# IO_FMU_REV_1B.net
KiCad netlist of a schematic drawn in Altium Designer
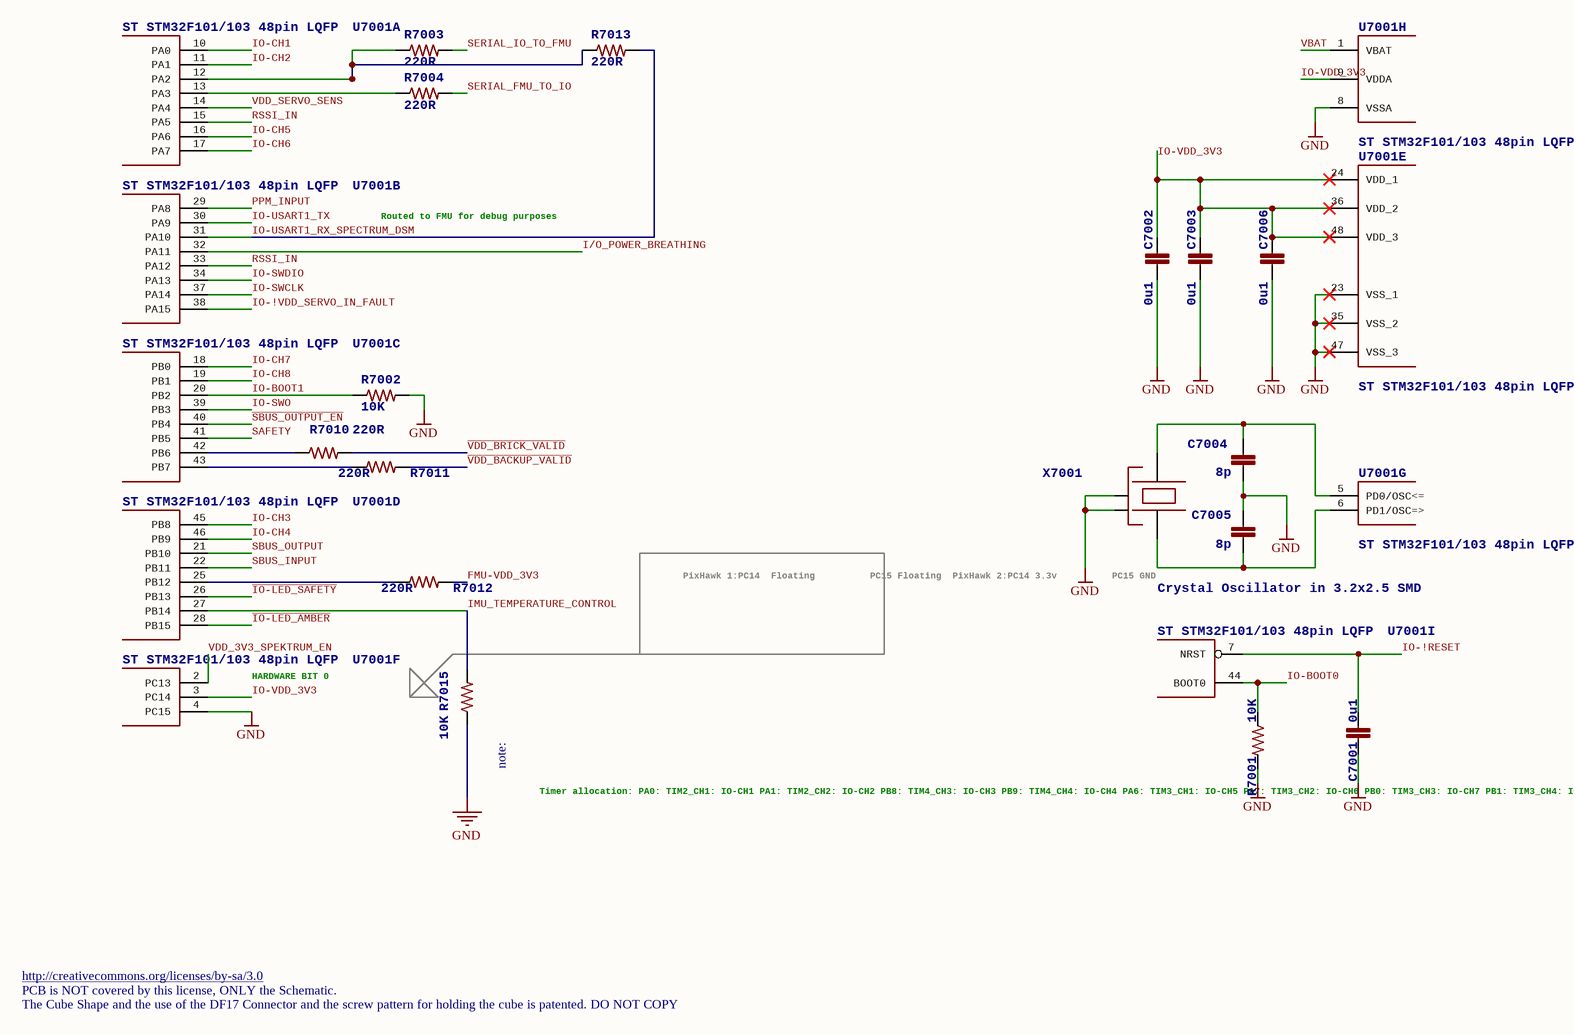
[diagram p0: IO_FMU_REV_1B.SchDoc]

(export (version "E")
  (design (tool "Eeschema 10.0.6"))
  (components
    (comp (ref "C7001")
      (value "0u1")
      (footprint "0402-CAP")
      (description "CAP CER 0.1UF 16V Y5V 0402")
      (libsource (lib "") (part "CAP0402_1"))
    )
    (comp (ref "C7002")
      (value "0u1")
      (footprint "0402-CAP")
      (description "CAP CER 0.1UF 16V Y5V 0402")
      (libsource (lib "pixhawk2") (part "CAP0402"))
    )
    (comp (ref "C7003")
      (value "0u1")
      (footprint "0402-CAP")
      (description "CAP CER 0.1UF 16V Y5V 0402")
      (libsource (lib "pixhawk2") (part "CAP0402"))
    )
    (comp (ref "C7004")
      (value "8p")
      (footprint "0402-CAP")
      (description "CAP CER 8PF 50V C0G 0402")
      (libsource (lib "pixhawk2") (part "CAP0402"))
    )
    (comp (ref "C7005")
      (value "8p")
      (footprint "0402-CAP")
      (description "CAP CER 8PF 50V C0G 0402")
      (libsource (lib "pixhawk2") (part "CAP0402"))
    )
    (comp (ref "C7006")
      (value "0u1")
      (footprint "0402-CAP")
      (description "CAP CER 0.1UF 16V Y5V 0402")
      (libsource (lib "pixhawk2") (part "CAP0402"))
    )
    (comp (ref "R7001")
      (value "10K")
      (footprint "0402-RES")
      (description "RES 10K OHM 1/16W 1% 0402 SMD")
      (libsource (lib "pixhawk2") (part "RESISTOR0402-RES"))
    )
    (comp (ref "R7002")
      (value "10K")
      (footprint "0402-RES")
      (description "RES 10K OHM 1/16W 1% 0402 SMD")
      (libsource (lib "pixhawk2") (part "RESISTOR0402-RES"))
    )
    (comp (ref "R7003")
      (value "220R")
      (footprint "0402-RES")
      (description "RES 220 OHM 1/16W 1% 0402 SMD")
      (libsource (lib "pixhawk2") (part "RESISTOR0402-RES"))
    )
    (comp (ref "R7004")
      (value "220R")
      (footprint "0402-RES")
      (description "RES 220 OHM 1/16W 1% 0402 SMD")
      (libsource (lib "pixhawk2") (part "RESISTOR0402-RES"))
    )
    (comp (ref "R7010")
      (value "220R")
      (footprint "0402-RES")
      (description "RES 220 OHM 1/16W 1% 0402 SMD")
      (libsource (lib "pixhawk2") (part "RESISTOR0402-RES"))
    )
    (comp (ref "R7011")
      (value "220R")
      (footprint "0402-RES")
      (description "RES 220 OHM 1/16W 1% 0402 SMD")
      (libsource (lib "pixhawk2") (part "RESISTOR0402-RES"))
    )
    (comp (ref "R7012")
      (value "220R")
      (footprint "0402-RES")
      (description "RES 220 OHM 1/16W 1% 0402 SMD")
      (libsource (lib "pixhawk2") (part "RESISTOR0402-RES"))
    )
    (comp (ref "R7013")
      (value "220R")
      (footprint "0402-RES")
      (description "RES 220 OHM 1/16W 1% 0402 SMD")
      (libsource (lib "pixhawk2") (part "RESISTOR0402-RES"))
    )
    (comp (ref "R7015")
      (value "10K")
      (footprint "0402-RES")
      (description "RES 10K OHM 1/16W 1% 0402 SMD")
      (libsource (lib "pixhawk2") (part "RESISTOR0402-RES"))
    )
    (comp (ref "U7001")
      (value "ST STM32F101/103 48pin LQFP")
      (footprint "TQFP48")
      (description "MCU 32BIT ARM 64K FLASH 48LQFP")
      (libsource (lib "pixhawk2") (part "STM32F10XCXT6"))
    )
    (comp (ref "X7001")
      (value "Crystal Oscillator in 3.2x2.5 SMD")
      (footprint "OSCILLATOR-3.2X2.5")
      (description "CRYSTAL 24MHZ 8PF SMD")
      (libsource (lib "pixhawk2") (part "OSCILLATOR-3.2X2.5"))
    )
  )
  (nets
    (net (code "1") (name "/FMU-VDD_3V3") (class "Default")
      (node (ref "R7012") (pin "P$2") (pinfunction "2_P$2") (pintype "passive"))
    )
    (net (code "2") (name "/IMU_TEMPERATURE_CONTROL") (class "Default")
      (node (ref "R7015") (pin "P$2") (pinfunction "2_P$2") (pintype "passive"))
      (node (ref "U7001") (pin "27") (pinfunction "PB14_27") (pintype "passive"))
    )
    (net (code "3") (name "/IO-!RESET") (class "Default")
      (node (ref "C7001") (pin "P$2") (pinfunction "2_P$2") (pintype "passive"))
      (node (ref "U7001") (pin "7") (pinfunction "NRST_7") (pintype "passive"))
    )
    (net (code "4") (name "/IO-!VDD_SERVO_IN_FAULT") (class "Default")
      (node (ref "U7001") (pin "38") (pinfunction "PA15_38") (pintype "passive"))
    )
    (net (code "5") (name "/IO-BOOT0") (class "Default")
      (node (ref "R7001") (pin "P$1") (pinfunction "1_P$1") (pintype "passive"))
      (node (ref "U7001") (pin "44") (pinfunction "BOOT0_44") (pintype "passive"))
    )
    (net (code "6") (name "/IO-BOOT1") (class "Default")
      (node (ref "R7002") (pin "P$1") (pinfunction "1_P$1") (pintype "passive"))
      (node (ref "U7001") (pin "20") (pinfunction "PB2_20") (pintype "passive"))
    )
    (net (code "7") (name "/IO-CH1") (class "Default")
      (node (ref "U7001") (pin "10") (pinfunction "PA0_10") (pintype "passive"))
    )
    (net (code "8") (name "/IO-CH2") (class "Default")
      (node (ref "U7001") (pin "11") (pinfunction "PA1_11") (pintype "passive"))
    )
    (net (code "9") (name "/IO-CH3") (class "Default")
      (node (ref "U7001") (pin "45") (pinfunction "PB8_45") (pintype "passive"))
    )
    (net (code "10") (name "/IO-CH4") (class "Default")
      (node (ref "U7001") (pin "46") (pinfunction "PB9_46") (pintype "passive"))
    )
    (net (code "11") (name "/IO-CH5") (class "Default")
      (node (ref "U7001") (pin "16") (pinfunction "PA6_16") (pintype "passive"))
    )
    (net (code "12") (name "/IO-CH6") (class "Default")
      (node (ref "U7001") (pin "17") (pinfunction "PA7_17") (pintype "passive"))
    )
    (net (code "13") (name "/IO-CH7") (class "Default")
      (node (ref "U7001") (pin "18") (pinfunction "PB0_18") (pintype "passive"))
    )
    (net (code "14") (name "/IO-CH8") (class "Default")
      (node (ref "U7001") (pin "19") (pinfunction "PB1_19") (pintype "passive"))
    )
    (net (code "15") (name "/IO-SWCLK") (class "Default")
      (node (ref "U7001") (pin "37") (pinfunction "PA14_37") (pintype "passive"))
    )
    (net (code "16") (name "/IO-SWDIO") (class "Default")
      (node (ref "U7001") (pin "34") (pinfunction "PA13_34") (pintype "passive"))
    )
    (net (code "17") (name "/IO-SWO") (class "Default")
      (node (ref "U7001") (pin "39") (pinfunction "PB3_39") (pintype "passive"))
    )
    (net (code "18") (name "/IO-USART1_RX_SPECTRUM_DSM") (class "Default")
      (node (ref "R7013") (pin "P$2") (pinfunction "2_P$2") (pintype "passive"))
      (node (ref "U7001") (pin "31") (pinfunction "PA10_31") (pintype "passive"))
    )
    (net (code "19") (name "/IO-USART1_TX") (class "Default")
      (node (ref "U7001") (pin "30") (pinfunction "PA9_30") (pintype "passive"))
    )
    (net (code "20") (name "/IO-VDD_3V3") (class "Default")
      (node (ref "C7002") (pin "P$1") (pinfunction "1_P$1") (pintype "passive"))
      (node (ref "C7003") (pin "P$1") (pinfunction "1_P$1") (pintype "passive"))
      (node (ref "C7006") (pin "P$1") (pinfunction "1_P$1") (pintype "passive"))
      (node (ref "U7001") (pin "24") (pinfunction "VDD_1_24") (pintype "power_in"))
      (node (ref "U7001") (pin "3") (pinfunction "PC14_3") (pintype "passive"))
      (node (ref "U7001") (pin "36") (pinfunction "VDD_2_36") (pintype "power_in"))
      (node (ref "U7001") (pin "48") (pinfunction "VDD_3_48") (pintype "power_in"))
      (node (ref "U7001") (pin "9") (pinfunction "VDDA_9") (pintype "power_in"))
    )
    (net (code "21") (name "/I{slash}O_POWER_BREATHING") (class "Default")
      (node (ref "U7001") (pin "32") (pinfunction "PA11_32") (pintype "passive"))
    )
    (net (code "22") (name "/PPM_INPUT") (class "Default")
      (node (ref "U7001") (pin "29") (pinfunction "PA8_29") (pintype "passive"))
    )
    (net (code "23") (name "/RSSI_IN") (class "Default")
      (node (ref "U7001") (pin "15") (pinfunction "PA5_15") (pintype "passive"))
      (node (ref "U7001") (pin "33") (pinfunction "PA12_33") (pintype "passive"))
    )
    (net (code "24") (name "/SAFETY") (class "Default")
      (node (ref "U7001") (pin "41") (pinfunction "PB5_41") (pintype "passive"))
    )
    (net (code "25") (name "/SBUS_INPUT") (class "Default")
      (node (ref "U7001") (pin "22") (pinfunction "PB11_22") (pintype "passive"))
    )
    (net (code "26") (name "/SBUS_OUTPUT") (class "Default")
      (node (ref "U7001") (pin "21") (pinfunction "PB10_21") (pintype "passive"))
    )
    (net (code "27") (name "/SERIAL_FMU_TO_IO") (class "Default")
      (node (ref "R7004") (pin "P$2") (pinfunction "2_P$2") (pintype "passive"))
    )
    (net (code "28") (name "/SERIAL_IO_TO_FMU") (class "Default")
      (node (ref "R7003") (pin "P$2") (pinfunction "2_P$2") (pintype "passive"))
    )
    (net (code "29") (name "/VBAT") (class "Default")
      (node (ref "U7001") (pin "1") (pinfunction "VBAT_1") (pintype "power_in"))
    )
    (net (code "30") (name "/VDD_3V3_SPEKTRUM_EN") (class "Default")
      (node (ref "U7001") (pin "2") (pinfunction "PC13_2") (pintype "passive"))
    )
    (net (code "31") (name "/VDD_SERVO_SENS") (class "Default")
      (node (ref "U7001") (pin "14") (pinfunction "PA4_14") (pintype "passive"))
    )
    (net (code "32") (name "/~{IO-LED_AMBER}") (class "Default")
      (node (ref "U7001") (pin "28") (pinfunction "PB15_28") (pintype "passive"))
    )
    (net (code "33") (name "/~{IO-LED_SAFETY}") (class "Default")
      (node (ref "U7001") (pin "26") (pinfunction "PB13_26") (pintype "passive"))
    )
    (net (code "34") (name "/~{SBUS_OUTPUT_EN}") (class "Default")
      (node (ref "U7001") (pin "40") (pinfunction "PB4_40") (pintype "passive"))
    )
    (net (code "35") (name "/~{VDD_BACKUP_VALID}") (class "Default")
      (node (ref "R7011") (pin "P$2") (pinfunction "2_P$2") (pintype "passive"))
    )
    (net (code "36") (name "/~{VDD_BRICK_VALID}") (class "Default")
      (node (ref "R7010") (pin "P$2") (pinfunction "2_P$2") (pintype "passive"))
    )
    (net (code "37") (name "GND") (class "Default")
      (node (ref "C7001") (pin "P$1") (pinfunction "1_P$1") (pintype "passive"))
      (node (ref "C7002") (pin "P$2") (pinfunction "2_P$2") (pintype "passive"))
      (node (ref "C7003") (pin "P$2") (pinfunction "2_P$2") (pintype "passive"))
      (node (ref "C7004") (pin "P$2") (pinfunction "2_P$2") (pintype "passive"))
      (node (ref "C7005") (pin "P$1") (pinfunction "1_P$1") (pintype "passive"))
      (node (ref "C7006") (pin "P$2") (pinfunction "2_P$2") (pintype "passive"))
      (node (ref "R7001") (pin "P$2") (pinfunction "2_P$2") (pintype "passive"))
      (node (ref "R7002") (pin "P$2") (pinfunction "2_P$2") (pintype "passive"))
      (node (ref "R7015") (pin "P$1") (pinfunction "1_P$1") (pintype "passive"))
      (node (ref "U7001") (pin "23") (pinfunction "VSS_1_23") (pintype "power_in"))
      (node (ref "U7001") (pin "35") (pinfunction "VSS_2_35") (pintype "power_in"))
      (node (ref "U7001") (pin "4") (pinfunction "PC15_4") (pintype "passive"))
      (node (ref "U7001") (pin "47") (pinfunction "VSS_3_47") (pintype "power_in"))
      (node (ref "U7001") (pin "8") (pinfunction "VSSA_8") (pintype "power_in"))
      (node (ref "X7001") (pin "2") (pinfunction "NC_2_2") (pintype "open_emitter"))
      (node (ref "X7001") (pin "4") (pinfunction "NC_4_4") (pintype "open_emitter"))
    )
    (net (code "38") (name "Net-(C7004-1)") (class "Default")
      (node (ref "C7004") (pin "P$1") (pinfunction "1_P$1") (pintype "passive"))
      (node (ref "U7001") (pin "5") (pinfunction "PD0/OSC<=_5") (pintype "passive"))
      (node (ref "X7001") (pin "3") (pinfunction "3_3") (pintype "passive"))
    )
    (net (code "39") (name "Net-(C7005-2)") (class "Default")
      (node (ref "C7005") (pin "P$2") (pinfunction "2_P$2") (pintype "passive"))
      (node (ref "U7001") (pin "6") (pinfunction "PD1/OSC=>_6") (pintype "passive"))
      (node (ref "X7001") (pin "1") (pinfunction "1_1") (pintype "passive"))
    )
    (net (code "40") (name "Net-(R7003-1)") (class "Default")
      (node (ref "R7003") (pin "P$1") (pinfunction "1_P$1") (pintype "passive"))
      (node (ref "R7013") (pin "P$1") (pinfunction "1_P$1") (pintype "passive"))
      (node (ref "U7001") (pin "12") (pinfunction "PA2_12") (pintype "passive"))
    )
    (net (code "41") (name "Net-(R7004-1)") (class "Default")
      (node (ref "R7004") (pin "P$1") (pinfunction "1_P$1") (pintype "passive"))
      (node (ref "U7001") (pin "13") (pinfunction "PA3_13") (pintype "passive"))
    )
    (net (code "42") (name "Net-(R7010-1)") (class "Default")
      (node (ref "R7010") (pin "P$1") (pinfunction "1_P$1") (pintype "passive"))
      (node (ref "U7001") (pin "42") (pinfunction "PB6_42") (pintype "passive"))
    )
    (net (code "43") (name "Net-(R7011-1)") (class "Default")
      (node (ref "R7011") (pin "P$1") (pinfunction "1_P$1") (pintype "passive"))
      (node (ref "U7001") (pin "43") (pinfunction "PB7_43") (pintype "passive"))
    )
    (net (code "44") (name "Net-(R7012-1)") (class "Default")
      (node (ref "R7012") (pin "P$1") (pinfunction "1_P$1") (pintype "passive"))
      (node (ref "U7001") (pin "25") (pinfunction "PB12_25") (pintype "passive"))
    )
  )
)
